# SH11_-_Battery_Balancing.net
KiCad netlist of a schematic drawn in Altium Designer
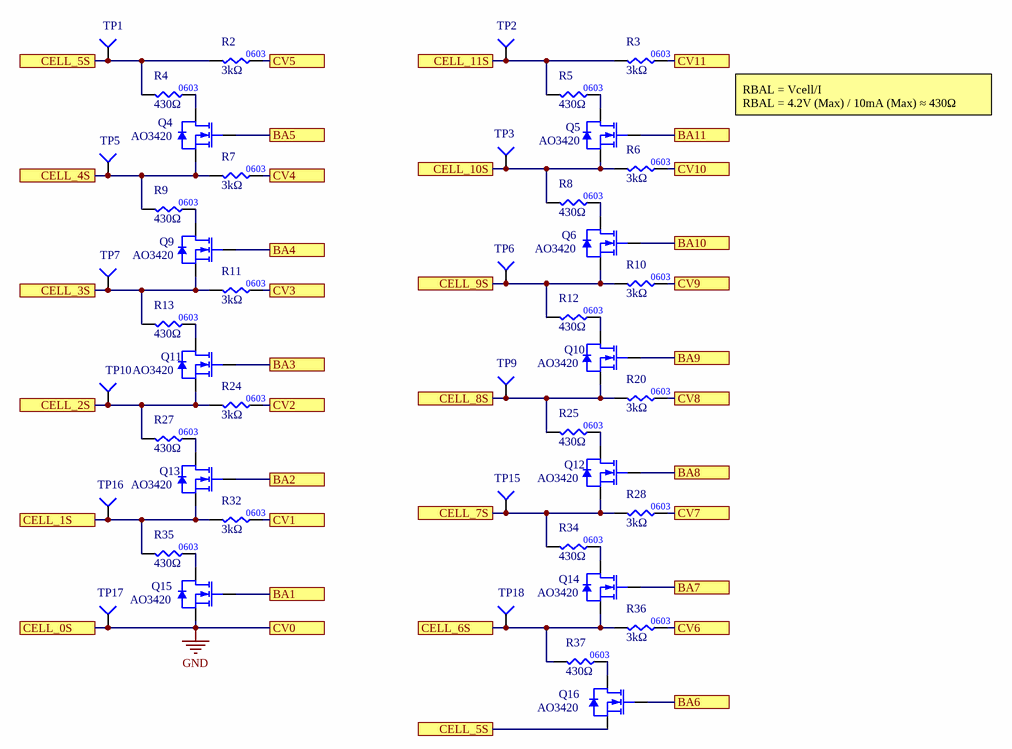
[diagram p0: SH11 - Battery Balancing.SchDoc]

(export (version "E")
  (design (tool "Eeschema 10.0.6"))
  (components
    (comp (ref "Q4")
      (value "NMOS_20V_6A")
      (footprint "SOT23-3")
      (description "MOSFET N-CH 20V 6A SOT-23")
      (fields (field (name "MANUFACTURER PART NUMBER 1") "AO3420"))
      (libsource (lib "UWRT_Schematic_Library_2020") (part "NMOS_20V_6A"))
    )
    (comp (ref "Q5")
      (value "NMOS_20V_6A")
      (footprint "SOT23-3")
      (description "MOSFET N-CH 20V 6A SOT-23")
      (fields (field (name "MANUFACTURER PART NUMBER 1") "AO3420"))
      (libsource (lib "UWRT_Schematic_Library_2020") (part "NMOS_20V_6A"))
    )
    (comp (ref "Q6")
      (value "NMOS_20V_6A")
      (footprint "SOT23-3")
      (description "MOSFET N-CH 20V 6A SOT-23")
      (fields (field (name "MANUFACTURER PART NUMBER 1") "AO3420"))
      (libsource (lib "UWRT_Schematic_Library_2020") (part "NMOS_20V_6A"))
    )
    (comp (ref "Q9")
      (value "NMOS_20V_6A")
      (footprint "SOT23-3")
      (description "MOSFET N-CH 20V 6A SOT-23")
      (fields (field (name "MANUFACTURER PART NUMBER 1") "AO3420"))
      (libsource (lib "UWRT_Schematic_Library_2020") (part "NMOS_20V_6A"))
    )
    (comp (ref "Q10")
      (value "NMOS_20V_6A")
      (footprint "SOT23-3")
      (description "MOSFET N-CH 20V 6A SOT-23")
      (fields (field (name "MANUFACTURER PART NUMBER 1") "AO3420"))
      (libsource (lib "UWRT_Schematic_Library_2020") (part "NMOS_20V_6A"))
    )
    (comp (ref "Q11")
      (value "NMOS_20V_6A")
      (footprint "SOT23-3")
      (description "MOSFET N-CH 20V 6A SOT-23")
      (fields (field (name "MANUFACTURER PART NUMBER 1") "AO3420"))
      (libsource (lib "UWRT_Schematic_Library_2020") (part "NMOS_20V_6A"))
    )
    (comp (ref "Q12")
      (value "NMOS_20V_6A")
      (footprint "SOT23-3")
      (description "MOSFET N-CH 20V 6A SOT-23")
      (fields (field (name "MANUFACTURER PART NUMBER 1") "AO3420"))
      (libsource (lib "UWRT_Schematic_Library_2020") (part "NMOS_20V_6A"))
    )
    (comp (ref "Q13")
      (value "NMOS_20V_6A")
      (footprint "SOT23-3")
      (description "MOSFET N-CH 20V 6A SOT-23")
      (fields (field (name "MANUFACTURER PART NUMBER 1") "AO3420"))
      (libsource (lib "UWRT_Schematic_Library_2020") (part "NMOS_20V_6A"))
    )
    (comp (ref "Q14")
      (value "NMOS_20V_6A")
      (footprint "SOT23-3")
      (description "MOSFET N-CH 20V 6A SOT-23")
      (fields (field (name "MANUFACTURER PART NUMBER 1") "AO3420"))
      (libsource (lib "UWRT_Schematic_Library_2020") (part "NMOS_20V_6A"))
    )
    (comp (ref "Q15")
      (value "NMOS_20V_6A")
      (footprint "SOT23-3")
      (description "MOSFET N-CH 20V 6A SOT-23")
      (fields (field (name "MANUFACTURER PART NUMBER 1") "AO3420"))
      (libsource (lib "UWRT_Schematic_Library_2020") (part "NMOS_20V_6A"))
    )
    (comp (ref "Q16")
      (value "NMOS_20V_6A")
      (footprint "SOT23-3")
      (description "MOSFET N-CH 20V 6A SOT-23")
      (fields (field (name "MANUFACTURER PART NUMBER 1") "AO3420"))
      (libsource (lib "UWRT_Schematic_Library_2020") (part "NMOS_20V_6A"))
    )
    (comp (ref "R2")
      (value "3kΩ")
      (footprint "RES0603")
      (description "RES 3K OHM 1% 1/10W 0603")
      (fields (field (name "Comment") "RES_3kΩ_0603_1%"))
      (libsource (lib "UWRT_Schematic_Library_2020") (part "RES_3kΩ_0603_1%"))
    )
    (comp (ref "R3")
      (value "3kΩ")
      (footprint "RES0603")
      (description "RES 3K OHM 1% 1/10W 0603")
      (fields (field (name "Comment") "RES_3kΩ_0603_1%"))
      (libsource (lib "UWRT_Schematic_Library_2020") (part "RES_3kΩ_0603_1%"))
    )
    (comp (ref "R4")
      (value "430Ω")
      (footprint "RES0603")
      (description "RES 430 OHM 5% 1/10W 0603")
      (fields (field (name "Comment") "RES_430Ω_0603_5%"))
      (libsource (lib "UWRT_Schematic_Library_2020") (part "RES_430Ω_0603_5%"))
    )
    (comp (ref "R5")
      (value "430Ω")
      (footprint "RES0603")
      (description "RES 430 OHM 5% 1/10W 0603")
      (fields (field (name "Comment") "RES_430Ω_0603_5%"))
      (libsource (lib "UWRT_Schematic_Library_2020") (part "RES_430Ω_0603_5%"))
    )
    (comp (ref "R6")
      (value "3kΩ")
      (footprint "RES0603")
      (description "RES 3K OHM 1% 1/10W 0603")
      (fields (field (name "Comment") "RES_3kΩ_0603_1%"))
      (libsource (lib "UWRT_Schematic_Library_2020") (part "RES_3kΩ_0603_1%"))
    )
    (comp (ref "R7")
      (value "3kΩ")
      (footprint "RES0603")
      (description "RES 3K OHM 1% 1/10W 0603")
      (fields (field (name "Comment") "RES_3kΩ_0603_1%"))
      (libsource (lib "UWRT_Schematic_Library_2020") (part "RES_3kΩ_0603_1%"))
    )
    (comp (ref "R8")
      (value "430Ω")
      (footprint "RES0603")
      (description "RES 430 OHM 5% 1/10W 0603")
      (fields (field (name "Comment") "RES_430Ω_0603_5%"))
      (libsource (lib "UWRT_Schematic_Library_2020") (part "RES_430Ω_0603_5%"))
    )
    (comp (ref "R9")
      (value "430Ω")
      (footprint "RES0603")
      (description "RES 430 OHM 5% 1/10W 0603")
      (fields (field (name "Comment") "RES_430Ω_0603_5%"))
      (libsource (lib "UWRT_Schematic_Library_2020") (part "RES_430Ω_0603_5%"))
    )
    (comp (ref "R10")
      (value "3kΩ")
      (footprint "RES0603")
      (description "RES 3K OHM 1% 1/10W 0603")
      (fields (field (name "Comment") "RES_3kΩ_0603_1%"))
      (libsource (lib "UWRT_Schematic_Library_2020") (part "RES_3kΩ_0603_1%"))
    )
    (comp (ref "R11")
      (value "3kΩ")
      (footprint "RES0603")
      (description "RES 3K OHM 1% 1/10W 0603")
      (fields (field (name "Comment") "RES_3kΩ_0603_1%"))
      (libsource (lib "UWRT_Schematic_Library_2020") (part "RES_3kΩ_0603_1%"))
    )
    (comp (ref "R12")
      (value "430Ω")
      (footprint "RES0603")
      (description "RES 430 OHM 5% 1/10W 0603")
      (fields (field (name "Comment") "RES_430Ω_0603_5%"))
      (libsource (lib "UWRT_Schematic_Library_2020") (part "RES_430Ω_0603_5%"))
    )
    (comp (ref "R13")
      (value "430Ω")
      (footprint "RES0603")
      (description "RES 430 OHM 5% 1/10W 0603")
      (fields (field (name "Comment") "RES_430Ω_0603_5%"))
      (libsource (lib "UWRT_Schematic_Library_2020") (part "RES_430Ω_0603_5%"))
    )
    (comp (ref "R20")
      (value "3kΩ")
      (footprint "RES0603")
      (description "RES 3K OHM 1% 1/10W 0603")
      (fields (field (name "Comment") "RES_3kΩ_0603_1%"))
      (libsource (lib "UWRT_Schematic_Library_2020") (part "RES_3kΩ_0603_1%"))
    )
    (comp (ref "R24")
      (value "3kΩ")
      (footprint "RES0603")
      (description "RES 3K OHM 1% 1/10W 0603")
      (fields (field (name "Comment") "RES_3kΩ_0603_1%"))
      (libsource (lib "UWRT_Schematic_Library_2020") (part "RES_3kΩ_0603_1%"))
    )
    (comp (ref "R25")
      (value "430Ω")
      (footprint "RES0603")
      (description "RES 430 OHM 5% 1/10W 0603")
      (fields (field (name "Comment") "RES_430Ω_0603_5%"))
      (libsource (lib "UWRT_Schematic_Library_2020") (part "RES_430Ω_0603_5%"))
    )
    (comp (ref "R27")
      (value "430Ω")
      (footprint "RES0603")
      (description "RES 430 OHM 5% 1/10W 0603")
      (fields (field (name "Comment") "RES_430Ω_0603_5%"))
      (libsource (lib "UWRT_Schematic_Library_2020") (part "RES_430Ω_0603_5%"))
    )
    (comp (ref "R28")
      (value "3kΩ")
      (footprint "RES0603")
      (description "RES 3K OHM 1% 1/10W 0603")
      (fields (field (name "Comment") "RES_3kΩ_0603_1%"))
      (libsource (lib "UWRT_Schematic_Library_2020") (part "RES_3kΩ_0603_1%"))
    )
    (comp (ref "R32")
      (value "3kΩ")
      (footprint "RES0603")
      (description "RES 3K OHM 1% 1/10W 0603")
      (fields (field (name "Comment") "RES_3kΩ_0603_1%"))
      (libsource (lib "UWRT_Schematic_Library_2020") (part "RES_3kΩ_0603_1%"))
    )
    (comp (ref "R34")
      (value "430Ω")
      (footprint "RES0603")
      (description "RES 430 OHM 5% 1/10W 0603")
      (fields (field (name "Comment") "RES_430Ω_0603_5%"))
      (libsource (lib "UWRT_Schematic_Library_2020") (part "RES_430Ω_0603_5%"))
    )
    (comp (ref "R35")
      (value "430Ω")
      (footprint "RES0603")
      (description "RES 430 OHM 5% 1/10W 0603")
      (fields (field (name "Comment") "RES_430Ω_0603_5%"))
      (libsource (lib "UWRT_Schematic_Library_2020") (part "RES_430Ω_0603_5%"))
    )
    (comp (ref "R36")
      (value "3kΩ")
      (footprint "RES0603")
      (description "RES 3K OHM 1% 1/10W 0603")
      (fields (field (name "Comment") "RES_3kΩ_0603_1%"))
      (libsource (lib "UWRT_Schematic_Library_2020") (part "RES_3kΩ_0603_1%"))
    )
    (comp (ref "R37")
      (value "430Ω")
      (footprint "RES0603")
      (description "RES 430 OHM 5% 1/10W 0603")
      (fields (field (name "Comment") "RES_430Ω_0603_5%"))
      (libsource (lib "UWRT_Schematic_Library_2020") (part "RES_430Ω_0603_5%"))
    )
    (comp (ref "TP1")
      (value "TESTPOINT_1MM_SQUARE")
      (footprint "TESTPOINT_SQUARE_1MM")
      (description "CELL5")
      (libsource (lib "UWRT_Schematic_Library_2020") (part "TESTPOINT_1MM_SQUARE"))
    )
    (comp (ref "TP2")
      (value "TESTPOINT_1MM_SQUARE")
      (footprint "TESTPOINT_SQUARE_1MM")
      (description "CELL11")
      (libsource (lib "UWRT_Schematic_Library_2020") (part "TESTPOINT_1MM_SQUARE"))
    )
    (comp (ref "TP3")
      (value "TESTPOINT_1MM_SQUARE")
      (footprint "TESTPOINT_SQUARE_1MM")
      (description "CELL10")
      (libsource (lib "UWRT_Schematic_Library_2020") (part "TESTPOINT_1MM_SQUARE"))
    )
    (comp (ref "TP5")
      (value "TESTPOINT_1MM_SQUARE")
      (footprint "TESTPOINT_SQUARE_1MM")
      (description "CELL4")
      (libsource (lib "UWRT_Schematic_Library_2020") (part "TESTPOINT_1MM_SQUARE"))
    )
    (comp (ref "TP6")
      (value "TESTPOINT_1MM_SQUARE")
      (footprint "TESTPOINT_SQUARE_1MM")
      (description "CELL9")
      (libsource (lib "UWRT_Schematic_Library_2020") (part "TESTPOINT_1MM_SQUARE"))
    )
    (comp (ref "TP7")
      (value "TESTPOINT_1MM_SQUARE")
      (footprint "TESTPOINT_SQUARE_1MM")
      (description "CELL3")
      (libsource (lib "UWRT_Schematic_Library_2020") (part "TESTPOINT_1MM_SQUARE"))
    )
    (comp (ref "TP9")
      (value "TESTPOINT_1MM_SQUARE")
      (footprint "TESTPOINT_SQUARE_1MM")
      (description "CELL8")
      (libsource (lib "UWRT_Schematic_Library_2020") (part "TESTPOINT_1MM_SQUARE"))
    )
    (comp (ref "TP10")
      (value "TESTPOINT_1MM_SQUARE")
      (footprint "TESTPOINT_SQUARE_1MM")
      (description "CELL2")
      (libsource (lib "UWRT_Schematic_Library_2020") (part "TESTPOINT_1MM_SQUARE"))
    )
    (comp (ref "TP15")
      (value "TESTPOINT_1MM_SQUARE")
      (footprint "TESTPOINT_SQUARE_1MM")
      (description "CELL7")
      (libsource (lib "UWRT_Schematic_Library_2020") (part "TESTPOINT_1MM_SQUARE"))
    )
    (comp (ref "TP16")
      (value "TESTPOINT_1MM_SQUARE")
      (footprint "TESTPOINT_SQUARE_1MM")
      (description "CELL1")
      (libsource (lib "UWRT_Schematic_Library_2020") (part "TESTPOINT_1MM_SQUARE"))
    )
    (comp (ref "TP17")
      (value "TESTPOINT_1MM_SQUARE")
      (footprint "TESTPOINT_SQUARE_1MM")
      (description "CELL0")
      (libsource (lib "UWRT_Schematic_Library_2020") (part "TESTPOINT_1MM_SQUARE"))
    )
    (comp (ref "TP18")
      (value "TESTPOINT_1MM_SQUARE")
      (footprint "TESTPOINT_SQUARE_1MM")
      (description "CELL6")
      (libsource (lib "UWRT_Schematic_Library_2020") (part "TESTPOINT_1MM_SQUARE"))
    )
  )
  (nets
    (net (code "1") (name "/BA1") (class "Default")
      (node (ref "Q15") (pin "1") (pinfunction "GATE_1") (pintype "passive"))
    )
    (net (code "2") (name "/BA2") (class "Default")
      (node (ref "Q13") (pin "1") (pinfunction "GATE_1") (pintype "passive"))
    )
    (net (code "3") (name "/BA3") (class "Default")
      (node (ref "Q11") (pin "1") (pinfunction "GATE_1") (pintype "passive"))
    )
    (net (code "4") (name "/BA4") (class "Default")
      (node (ref "Q9") (pin "1") (pinfunction "GATE_1") (pintype "passive"))
    )
    (net (code "5") (name "/BA5") (class "Default")
      (node (ref "Q4") (pin "1") (pinfunction "GATE_1") (pintype "passive"))
    )
    (net (code "6") (name "/BA6") (class "Default")
      (node (ref "Q16") (pin "1") (pinfunction "GATE_1") (pintype "passive"))
    )
    (net (code "7") (name "/BA7") (class "Default")
      (node (ref "Q14") (pin "1") (pinfunction "GATE_1") (pintype "passive"))
    )
    (net (code "8") (name "/BA8") (class "Default")
      (node (ref "Q12") (pin "1") (pinfunction "GATE_1") (pintype "passive"))
    )
    (net (code "9") (name "/BA9") (class "Default")
      (node (ref "Q10") (pin "1") (pinfunction "GATE_1") (pintype "passive"))
    )
    (net (code "10") (name "/BA10") (class "Default")
      (node (ref "Q6") (pin "1") (pinfunction "GATE_1") (pintype "passive"))
    )
    (net (code "11") (name "/BA11") (class "Default")
      (node (ref "Q5") (pin "1") (pinfunction "GATE_1") (pintype "passive"))
    )
    (net (code "12") (name "/CELL_1S") (class "Default")
      (node (ref "Q13") (pin "2") (pinfunction "SOURCE_2") (pintype "passive"))
      (node (ref "R32") (pin "1") (pinfunction "1_1") (pintype "passive"))
      (node (ref "R35") (pin "1") (pinfunction "1_1") (pintype "passive"))
      (node (ref "TP16") (pin "1") (pinfunction "=value_1") (pintype "passive"))
    )
    (net (code "13") (name "/CELL_2S") (class "Default")
      (node (ref "Q11") (pin "2") (pinfunction "SOURCE_2") (pintype "passive"))
      (node (ref "R24") (pin "1") (pinfunction "1_1") (pintype "passive"))
      (node (ref "R27") (pin "1") (pinfunction "1_1") (pintype "passive"))
      (node (ref "TP10") (pin "1") (pinfunction "=value_1") (pintype "passive"))
    )
    (net (code "14") (name "/CELL_3S") (class "Default")
      (node (ref "Q9") (pin "2") (pinfunction "SOURCE_2") (pintype "passive"))
      (node (ref "R11") (pin "1") (pinfunction "1_1") (pintype "passive"))
      (node (ref "R13") (pin "1") (pinfunction "1_1") (pintype "passive"))
      (node (ref "TP7") (pin "1") (pinfunction "=value_1") (pintype "passive"))
    )
    (net (code "15") (name "/CELL_4S") (class "Default")
      (node (ref "Q4") (pin "2") (pinfunction "SOURCE_2") (pintype "passive"))
      (node (ref "R7") (pin "1") (pinfunction "1_1") (pintype "passive"))
      (node (ref "R9") (pin "1") (pinfunction "1_1") (pintype "passive"))
      (node (ref "TP5") (pin "1") (pinfunction "=value_1") (pintype "passive"))
    )
    (net (code "16") (name "/CELL_5S") (class "Default")
      (node (ref "Q16") (pin "2") (pinfunction "SOURCE_2") (pintype "passive"))
      (node (ref "R2") (pin "1") (pinfunction "1_1") (pintype "passive"))
      (node (ref "R4") (pin "1") (pinfunction "1_1") (pintype "passive"))
      (node (ref "TP1") (pin "1") (pinfunction "=value_1") (pintype "passive"))
    )
    (net (code "17") (name "/CELL_6S") (class "Default")
      (node (ref "Q14") (pin "2") (pinfunction "SOURCE_2") (pintype "passive"))
      (node (ref "R36") (pin "1") (pinfunction "1_1") (pintype "passive"))
      (node (ref "R37") (pin "1") (pinfunction "1_1") (pintype "passive"))
      (node (ref "TP18") (pin "1") (pinfunction "=value_1") (pintype "passive"))
    )
    (net (code "18") (name "/CELL_7S") (class "Default")
      (node (ref "Q12") (pin "2") (pinfunction "SOURCE_2") (pintype "passive"))
      (node (ref "R28") (pin "1") (pinfunction "1_1") (pintype "passive"))
      (node (ref "R34") (pin "1") (pinfunction "1_1") (pintype "passive"))
      (node (ref "TP15") (pin "1") (pinfunction "=value_1") (pintype "passive"))
    )
    (net (code "19") (name "/CELL_8S") (class "Default")
      (node (ref "Q10") (pin "2") (pinfunction "SOURCE_2") (pintype "passive"))
      (node (ref "R20") (pin "1") (pinfunction "1_1") (pintype "passive"))
      (node (ref "R25") (pin "1") (pinfunction "1_1") (pintype "passive"))
      (node (ref "TP9") (pin "1") (pinfunction "=value_1") (pintype "passive"))
    )
    (net (code "20") (name "/CELL_9S") (class "Default")
      (node (ref "Q6") (pin "2") (pinfunction "SOURCE_2") (pintype "passive"))
      (node (ref "R10") (pin "1") (pinfunction "1_1") (pintype "passive"))
      (node (ref "R12") (pin "1") (pinfunction "1_1") (pintype "passive"))
      (node (ref "TP6") (pin "1") (pinfunction "=value_1") (pintype "passive"))
    )
    (net (code "21") (name "/CELL_10S") (class "Default")
      (node (ref "Q5") (pin "2") (pinfunction "SOURCE_2") (pintype "passive"))
      (node (ref "R6") (pin "1") (pinfunction "1_1") (pintype "passive"))
      (node (ref "R8") (pin "1") (pinfunction "1_1") (pintype "passive"))
      (node (ref "TP3") (pin "1") (pinfunction "=value_1") (pintype "passive"))
    )
    (net (code "22") (name "/CELL_11S") (class "Default")
      (node (ref "R3") (pin "1") (pinfunction "1_1") (pintype "passive"))
      (node (ref "R5") (pin "1") (pinfunction "1_1") (pintype "passive"))
      (node (ref "TP2") (pin "1") (pinfunction "=value_1") (pintype "passive"))
    )
    (net (code "23") (name "/CV1") (class "Default")
      (node (ref "R32") (pin "2") (pinfunction "2_2") (pintype "passive"))
    )
    (net (code "24") (name "/CV2") (class "Default")
      (node (ref "R24") (pin "2") (pinfunction "2_2") (pintype "passive"))
    )
    (net (code "25") (name "/CV3") (class "Default")
      (node (ref "R11") (pin "2") (pinfunction "2_2") (pintype "passive"))
    )
    (net (code "26") (name "/CV4") (class "Default")
      (node (ref "R7") (pin "2") (pinfunction "2_2") (pintype "passive"))
    )
    (net (code "27") (name "/CV5") (class "Default")
      (node (ref "R2") (pin "2") (pinfunction "2_2") (pintype "passive"))
    )
    (net (code "28") (name "/CV6") (class "Default")
      (node (ref "R36") (pin "2") (pinfunction "2_2") (pintype "passive"))
    )
    (net (code "29") (name "/CV7") (class "Default")
      (node (ref "R28") (pin "2") (pinfunction "2_2") (pintype "passive"))
    )
    (net (code "30") (name "/CV8") (class "Default")
      (node (ref "R20") (pin "2") (pinfunction "2_2") (pintype "passive"))
    )
    (net (code "31") (name "/CV9") (class "Default")
      (node (ref "R10") (pin "2") (pinfunction "2_2") (pintype "passive"))
    )
    (net (code "32") (name "/CV10") (class "Default")
      (node (ref "R6") (pin "2") (pinfunction "2_2") (pintype "passive"))
    )
    (net (code "33") (name "/CV11") (class "Default")
      (node (ref "R3") (pin "2") (pinfunction "2_2") (pintype "passive"))
    )
    (net (code "34") (name "GND") (class "Default")
      (node (ref "Q15") (pin "2") (pinfunction "SOURCE_2") (pintype "passive"))
      (node (ref "TP17") (pin "1") (pinfunction "=value_1") (pintype "passive"))
    )
    (net (code "35") (name "Net-(Q4-DRAIN)") (class "Default")
      (node (ref "Q4") (pin "3") (pinfunction "DRAIN_3") (pintype "passive"))
      (node (ref "R4") (pin "2") (pinfunction "2_2") (pintype "passive"))
    )
    (net (code "36") (name "Net-(Q5-DRAIN)") (class "Default")
      (node (ref "Q5") (pin "3") (pinfunction "DRAIN_3") (pintype "passive"))
      (node (ref "R5") (pin "2") (pinfunction "2_2") (pintype "passive"))
    )
    (net (code "37") (name "Net-(Q6-DRAIN)") (class "Default")
      (node (ref "Q6") (pin "3") (pinfunction "DRAIN_3") (pintype "passive"))
      (node (ref "R8") (pin "2") (pinfunction "2_2") (pintype "passive"))
    )
    (net (code "38") (name "Net-(Q9-DRAIN)") (class "Default")
      (node (ref "Q9") (pin "3") (pinfunction "DRAIN_3") (pintype "passive"))
      (node (ref "R9") (pin "2") (pinfunction "2_2") (pintype "passive"))
    )
    (net (code "39") (name "Net-(Q10-DRAIN)") (class "Default")
      (node (ref "Q10") (pin "3") (pinfunction "DRAIN_3") (pintype "passive"))
      (node (ref "R12") (pin "2") (pinfunction "2_2") (pintype "passive"))
    )
    (net (code "40") (name "Net-(Q11-DRAIN)") (class "Default")
      (node (ref "Q11") (pin "3") (pinfunction "DRAIN_3") (pintype "passive"))
      (node (ref "R13") (pin "2") (pinfunction "2_2") (pintype "passive"))
    )
    (net (code "41") (name "Net-(Q12-DRAIN)") (class "Default")
      (node (ref "Q12") (pin "3") (pinfunction "DRAIN_3") (pintype "passive"))
      (node (ref "R25") (pin "2") (pinfunction "2_2") (pintype "passive"))
    )
    (net (code "42") (name "Net-(Q13-DRAIN)") (class "Default")
      (node (ref "Q13") (pin "3") (pinfunction "DRAIN_3") (pintype "passive"))
      (node (ref "R27") (pin "2") (pinfunction "2_2") (pintype "passive"))
    )
    (net (code "43") (name "Net-(Q14-DRAIN)") (class "Default")
      (node (ref "Q14") (pin "3") (pinfunction "DRAIN_3") (pintype "passive"))
      (node (ref "R34") (pin "2") (pinfunction "2_2") (pintype "passive"))
    )
    (net (code "44") (name "Net-(Q15-DRAIN)") (class "Default")
      (node (ref "Q15") (pin "3") (pinfunction "DRAIN_3") (pintype "passive"))
      (node (ref "R35") (pin "2") (pinfunction "2_2") (pintype "passive"))
    )
    (net (code "45") (name "Net-(Q16-DRAIN)") (class "Default")
      (node (ref "Q16") (pin "3") (pinfunction "DRAIN_3") (pintype "passive"))
      (node (ref "R37") (pin "2") (pinfunction "2_2") (pintype "passive"))
    )
  )
)
